# annoy-o-tron.net
KiCad netlist of a schematic drawn in EAGLE
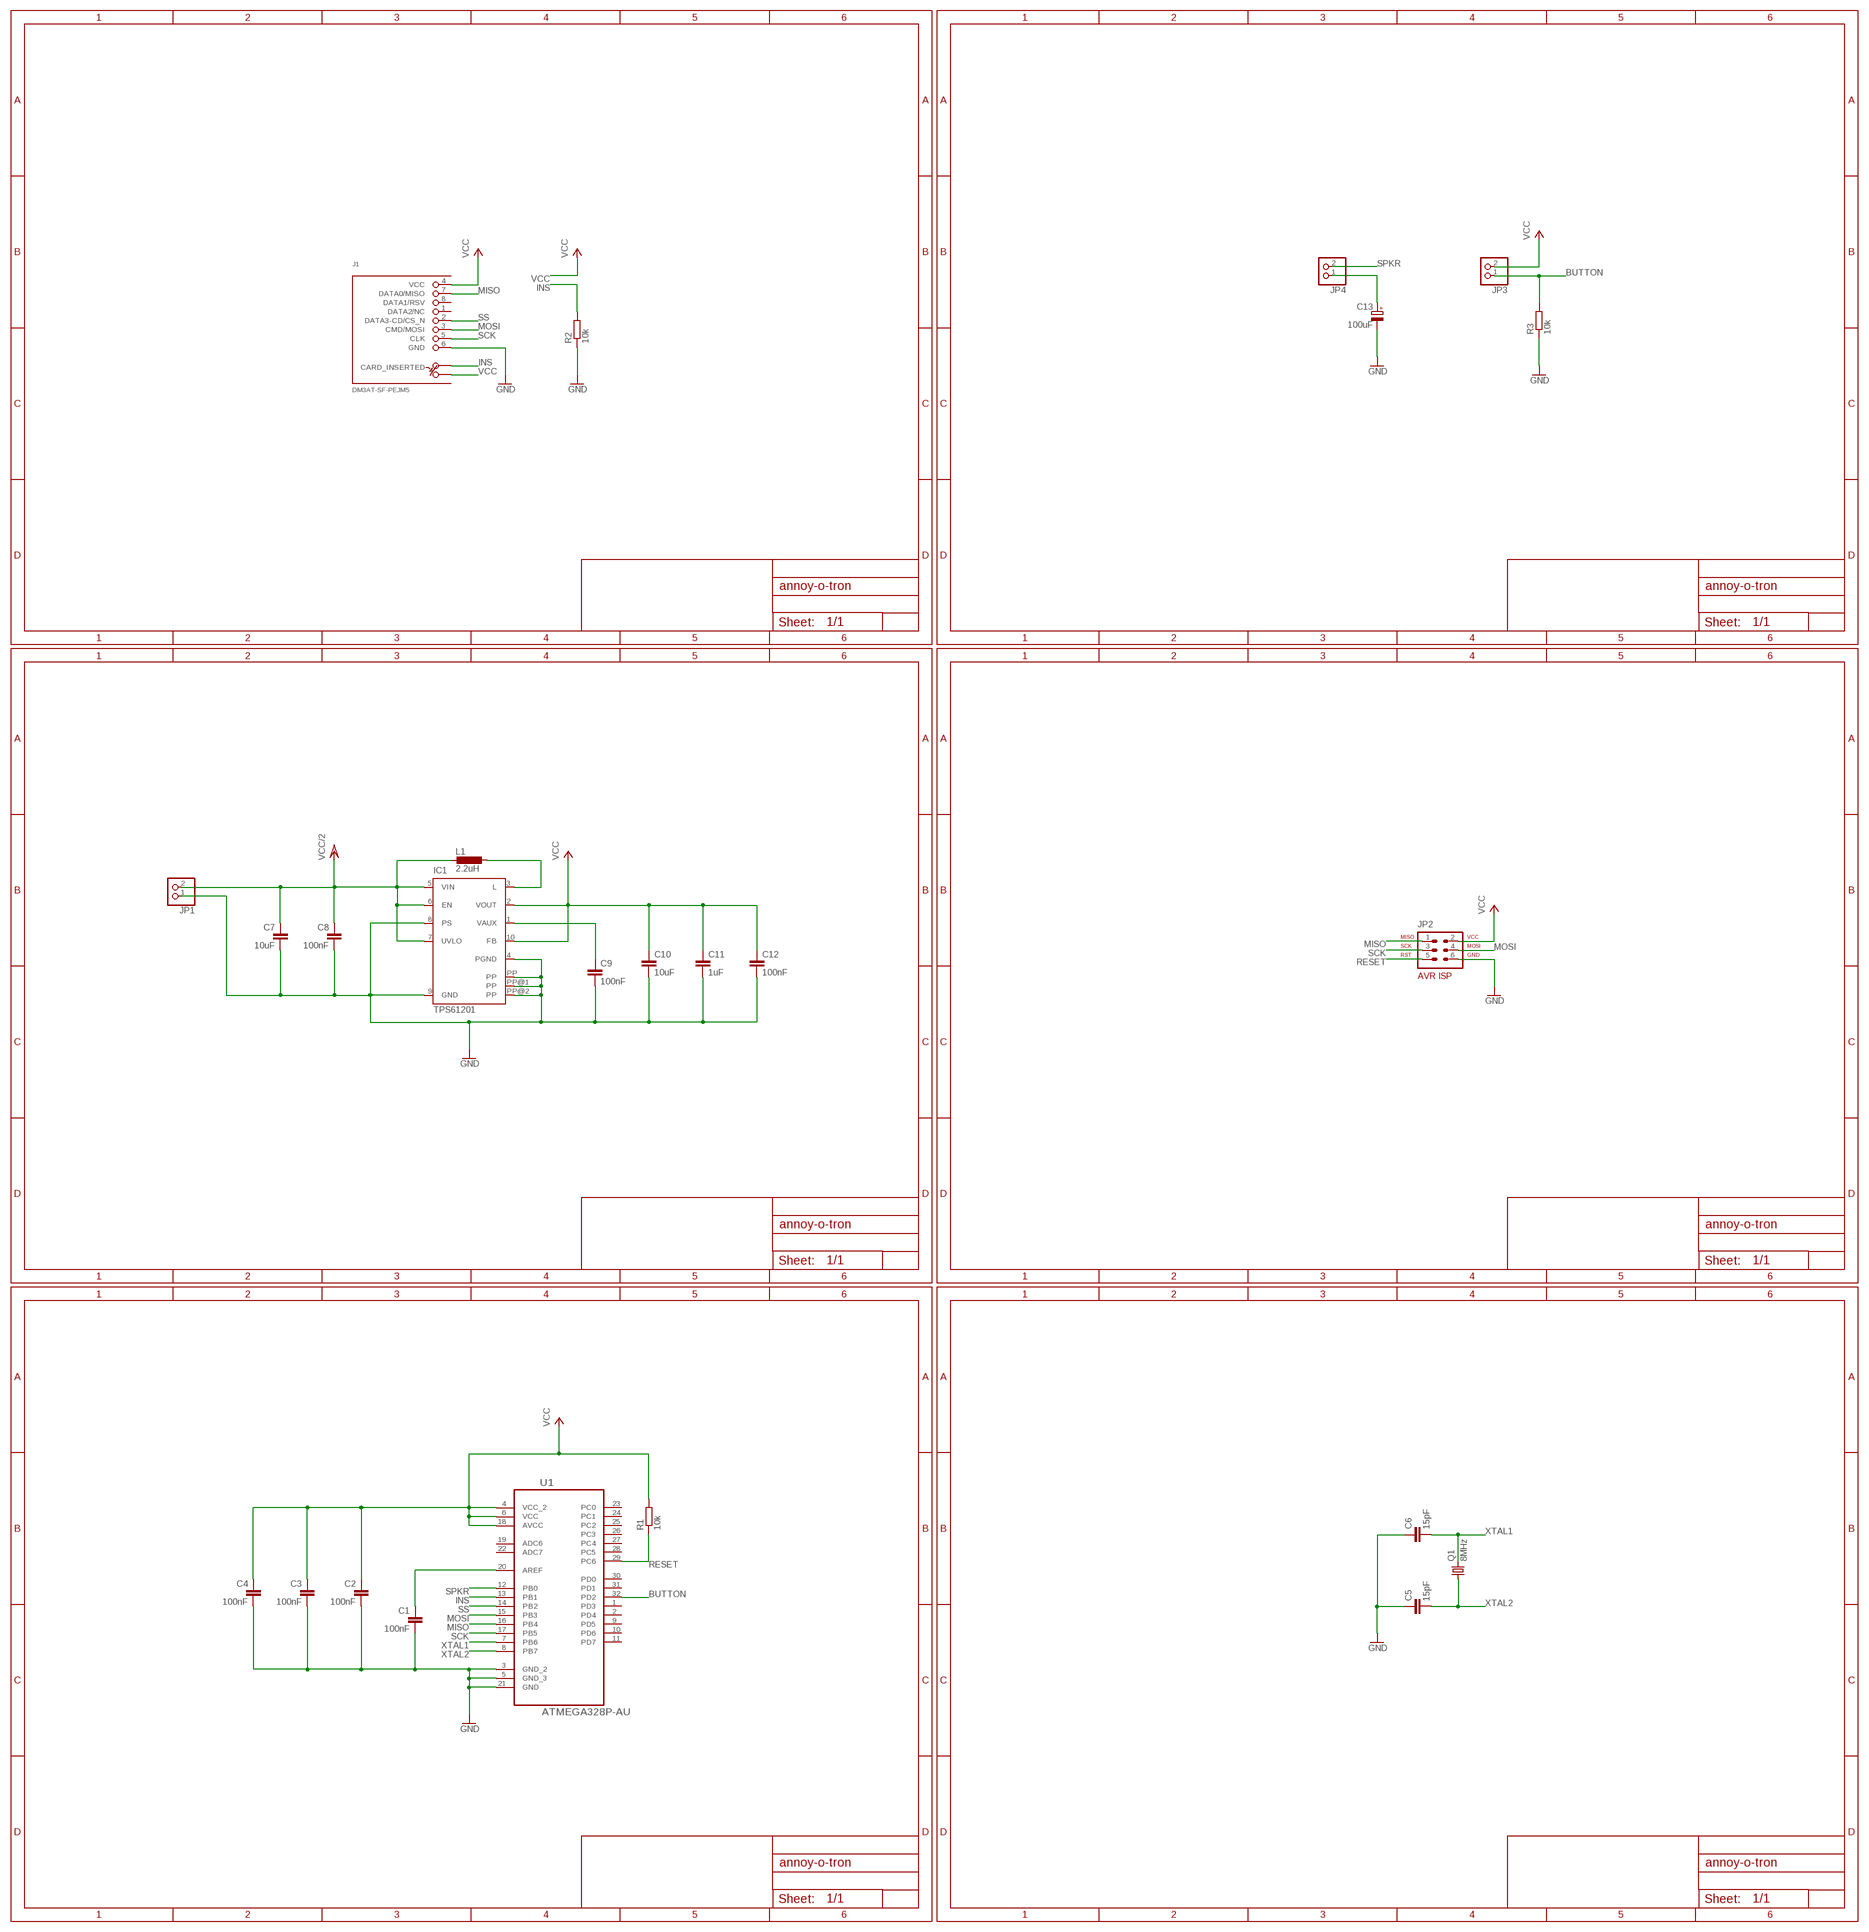
[diagram p0: schematic, sheet 1]

(export (version "E")
  (design (tool "Eeschema 10.0.6"))
  (components
    (comp (ref "C1")
      (value "100nF")
      (footprint "eagle-import:C0805K")
      (libsource (lib "eagle-import") (part "C-EUC0805K"))
    )
    (comp (ref "C2")
      (value "100nF")
      (footprint "eagle-import:C0805K")
      (libsource (lib "eagle-import") (part "C-EUC0805K"))
    )
    (comp (ref "C3")
      (value "100nF")
      (footprint "eagle-import:C0805K")
      (libsource (lib "eagle-import") (part "C-EUC0805K"))
    )
    (comp (ref "C4")
      (value "100nF")
      (footprint "eagle-import:C0805K")
      (libsource (lib "eagle-import") (part "C-EUC0805K"))
    )
    (comp (ref "C5")
      (value "15pF")
      (footprint "eagle-import:C0805K")
      (libsource (lib "eagle-import") (part "C-EUC0805K"))
    )
    (comp (ref "C6")
      (value "15pF")
      (footprint "eagle-import:C0805K")
      (libsource (lib "eagle-import") (part "C-EUC0805K"))
    )
    (comp (ref "C7")
      (value "10uF")
      (footprint "eagle-import:C0805K")
      (libsource (lib "eagle-import") (part "C-EUC0805K"))
    )
    (comp (ref "C8")
      (value "100nF")
      (footprint "eagle-import:C0805K")
      (libsource (lib "eagle-import") (part "C-EUC0805K"))
    )
    (comp (ref "C9")
      (value "100nF")
      (footprint "eagle-import:C0805K")
      (libsource (lib "eagle-import") (part "C-EUC0805K"))
    )
    (comp (ref "C10")
      (value "10uF")
      (footprint "eagle-import:C0805K")
      (libsource (lib "eagle-import") (part "C-EUC0805K"))
    )
    (comp (ref "C11")
      (value "1uF")
      (footprint "eagle-import:C0805K")
      (libsource (lib "eagle-import") (part "C-EUC0805K"))
    )
    (comp (ref "C12")
      (value "100nF")
      (footprint "eagle-import:C0805K")
      (libsource (lib "eagle-import") (part "C-EUC0805K"))
    )
    (comp (ref "C13")
      (value "100uF")
      (footprint "eagle-import:153CLV-0405")
      (libsource (lib "eagle-import") (part "CPOL-EU153CLV-0405"))
    )
    (comp (ref "IC1")
      (value "TPS61201")
      (footprint "eagle-import:S-PDSO-N10")
      (fields (field (name "MPN") "TPS61201DRCT"))
      (libsource (lib "eagle-import") (part "TPS61201"))
    )
    (comp (ref "J1")
      (value "DM3AT-SF-PEJM5")
      (footprint "eagle-import:DM3AT-SF-PEJM5")
      (libsource (lib "eagle-import") (part "DM3AT-SF-PEJM5"))
    )
    (comp (ref "JP1")
      (value "PINHD-1X2")
      (footprint "eagle-import:1X02")
      (libsource (lib "eagle-import") (part "PINHD-1X2"))
    )
    (comp (ref "JP2")
      (value "AVR-ISP-6VERT")
      (footprint "eagle-import:AVR-ISP-6")
      (libsource (lib "eagle-import") (part "AVR-ISP-6VERT"))
    )
    (comp (ref "JP3")
      (value "PINHD-1X2")
      (footprint "eagle-import:1X02")
      (libsource (lib "eagle-import") (part "PINHD-1X2"))
    )
    (comp (ref "JP4")
      (value "PINHD-1X2")
      (footprint "eagle-import:1X02")
      (libsource (lib "eagle-import") (part "PINHD-1X2"))
    )
    (comp (ref "L1")
      (value "2.2uH")
      (footprint "eagle-import:SRN3012TA")
      (libsource (lib "eagle-import") (part "SRN3012TA"))
    )
    (comp (ref "Q1")
      (value "8MHz")
      (footprint "eagle-import:HC49_S")
      (libsource (lib "eagle-import") (part "CRYSTALHC49S"))
    )
    (comp (ref "R1")
      (value "10k")
      (footprint "eagle-import:R0805")
      (libsource (lib "eagle-import") (part "R-EU_R0805"))
    )
    (comp (ref "R2")
      (value "10k")
      (footprint "eagle-import:R0805")
      (libsource (lib "eagle-import") (part "R-EU_R0805"))
    )
    (comp (ref "R3")
      (value "10k")
      (footprint "eagle-import:R0805")
      (libsource (lib "eagle-import") (part "R-EU_R0805"))
    )
    (comp (ref "U1")
      (value "ATMEGA328P-AU")
      (footprint "eagle-import:QFP80P900X900X120-32N")
      (libsource (lib "eagle-import") (part "ATMEGA328P-AU"))
    )
  )
  (nets
    (net (code "1") (name "/BUTTON") (class "Default")
      (node (ref "JP3") (pin "1") (pinfunction "1_1") (pintype "passive"))
      (node (ref "R3") (pin "2") (pinfunction "2_2") (pintype "passive"))
      (node (ref "U1") (pin "32") (pinfunction "PD2_32") (pintype "bidirectional"))
    )
    (net (code "2") (name "/INS") (class "Default")
      (node (ref "J1") (pin "A") (pinfunction "A_A") (pintype "bidirectional"))
      (node (ref "R2") (pin "2") (pinfunction "2_2") (pintype "passive"))
      (node (ref "U1") (pin "13") (pinfunction "PB1_13") (pintype "bidirectional"))
    )
    (net (code "3") (name "/MISO") (class "Default")
      (node (ref "J1") (pin "7") (pinfunction "DATA0/MISO_7") (pintype "bidirectional"))
      (node (ref "JP2") (pin "1") (pinfunction "1_1") (pintype "passive"))
      (node (ref "U1") (pin "16") (pinfunction "PB4_16") (pintype "bidirectional"))
    )
    (net (code "4") (name "/MOSI") (class "Default")
      (node (ref "J1") (pin "3") (pinfunction "CMD/MOSI_3") (pintype "bidirectional"))
      (node (ref "JP2") (pin "4") (pinfunction "4_4") (pintype "passive"))
      (node (ref "U1") (pin "15") (pinfunction "PB3_15") (pintype "bidirectional"))
    )
    (net (code "5") (name "/RESET") (class "Default")
      (node (ref "JP2") (pin "5") (pinfunction "5_5") (pintype "passive"))
      (node (ref "R1") (pin "1") (pinfunction "1_1") (pintype "passive"))
      (node (ref "U1") (pin "29") (pinfunction "PC6_29") (pintype "bidirectional"))
    )
    (net (code "6") (name "/SCK") (class "Default")
      (node (ref "J1") (pin "5") (pinfunction "CLK_5") (pintype "bidirectional"))
      (node (ref "JP2") (pin "3") (pinfunction "3_3") (pintype "passive"))
      (node (ref "U1") (pin "17") (pinfunction "PB5_17") (pintype "bidirectional"))
    )
    (net (code "7") (name "/SPKR") (class "Default")
      (node (ref "JP4") (pin "2") (pinfunction "2_2") (pintype "passive"))
      (node (ref "U1") (pin "12") (pinfunction "PB0_12") (pintype "bidirectional"))
    )
    (net (code "8") (name "/SS") (class "Default")
      (node (ref "J1") (pin "2") (pinfunction "DATA3-CD/CS_N_2") (pintype "bidirectional"))
      (node (ref "U1") (pin "14") (pinfunction "PB2_14") (pintype "bidirectional"))
    )
    (net (code "9") (name "/XTAL1") (class "Default")
      (node (ref "C6") (pin "2") (pinfunction "2_2") (pintype "passive"))
      (node (ref "Q1") (pin "2") (pinfunction "2_2") (pintype "passive"))
      (node (ref "U1") (pin "7") (pinfunction "PB6_7") (pintype "bidirectional"))
    )
    (net (code "10") (name "/XTAL2") (class "Default")
      (node (ref "C5") (pin "2") (pinfunction "2_2") (pintype "passive"))
      (node (ref "Q1") (pin "1") (pinfunction "1_1") (pintype "passive"))
      (node (ref "U1") (pin "8") (pinfunction "PB7_8") (pintype "bidirectional"))
    )
    (net (code "11") (name "GND") (class "Default")
      (node (ref "C1") (pin "2") (pinfunction "2_2") (pintype "passive"))
      (node (ref "C10") (pin "2") (pinfunction "2_2") (pintype "passive"))
      (node (ref "C11") (pin "2") (pinfunction "2_2") (pintype "passive"))
      (node (ref "C12") (pin "2") (pinfunction "2_2") (pintype "passive"))
      (node (ref "C13") (pin "-") (pinfunction "-_-") (pintype "passive"))
      (node (ref "C2") (pin "2") (pinfunction "2_2") (pintype "passive"))
      (node (ref "C3") (pin "2") (pinfunction "2_2") (pintype "passive"))
      (node (ref "C4") (pin "2") (pinfunction "2_2") (pintype "passive"))
      (node (ref "C5") (pin "1") (pinfunction "1_1") (pintype "passive"))
      (node (ref "C6") (pin "1") (pinfunction "1_1") (pintype "passive"))
      (node (ref "C7") (pin "2") (pinfunction "2_2") (pintype "passive"))
      (node (ref "C8") (pin "2") (pinfunction "2_2") (pintype "passive"))
      (node (ref "C9") (pin "2") (pinfunction "2_2") (pintype "passive"))
      (node (ref "IC1") (pin "4") (pinfunction "PGND_4") (pintype "power_in"))
      (node (ref "IC1") (pin "8") (pinfunction "PS_8") (pintype "input"))
      (node (ref "IC1") (pin "9") (pinfunction "GND_9") (pintype "power_in"))
      (node (ref "IC1") (pin "PP") (pinfunction "PP_PP") (pintype "power_in"))
      (node (ref "IC1") (pin "PP@1") (pinfunction "PP_PP@1") (pintype "power_in"))
      (node (ref "IC1") (pin "PP@2") (pinfunction "PP_PP@2") (pintype "power_in"))
      (node (ref "J1") (pin "6") (pinfunction "GND_6") (pintype "bidirectional"))
      (node (ref "JP1") (pin "1") (pinfunction "1_1") (pintype "passive"))
      (node (ref "JP2") (pin "6") (pinfunction "6_6") (pintype "passive"))
      (node (ref "R2") (pin "1") (pinfunction "1_1") (pintype "passive"))
      (node (ref "R3") (pin "1") (pinfunction "1_1") (pintype "passive"))
      (node (ref "U1") (pin "21") (pinfunction "GND_21") (pintype "passive"))
      (node (ref "U1") (pin "3") (pinfunction "GND_2_3") (pintype "passive"))
      (node (ref "U1") (pin "5") (pinfunction "GND_3_5") (pintype "passive"))
    )
    (net (code "12") (name "Net-(C13-Pad+)") (class "Default")
      (node (ref "C13") (pin "+") (pinfunction "+_+") (pintype "passive"))
      (node (ref "JP4") (pin "1") (pinfunction "1_1") (pintype "passive"))
    )
    (net (code "13") (name "Net-(IC1-L)") (class "Default")
      (node (ref "IC1") (pin "3") (pinfunction "L_3") (pintype "input"))
      (node (ref "L1") (pin "P$1") (pinfunction "1_P$1") (pintype "passive"))
    )
    (net (code "14") (name "Net-(IC1-VAUX)") (class "Default")
      (node (ref "C9") (pin "1") (pinfunction "1_1") (pintype "passive"))
      (node (ref "IC1") (pin "1") (pinfunction "VAUX_1") (pintype "bidirectional"))
    )
    (net (code "15") (name "Net-(U1-AREF)") (class "Default")
      (node (ref "C1") (pin "1") (pinfunction "1_1") (pintype "passive"))
      (node (ref "U1") (pin "20") (pinfunction "AREF_20") (pintype "input"))
    )
    (net (code "16") (name "VCC") (class "Default")
      (node (ref "C10") (pin "1") (pinfunction "1_1") (pintype "passive"))
      (node (ref "C11") (pin "1") (pinfunction "1_1") (pintype "passive"))
      (node (ref "C12") (pin "1") (pinfunction "1_1") (pintype "passive"))
      (node (ref "C2") (pin "1") (pinfunction "1_1") (pintype "passive"))
      (node (ref "C3") (pin "1") (pinfunction "1_1") (pintype "passive"))
      (node (ref "C4") (pin "1") (pinfunction "1_1") (pintype "passive"))
      (node (ref "IC1") (pin "10") (pinfunction "FB_10") (pintype "input"))
      (node (ref "IC1") (pin "2") (pinfunction "VOUT_2") (pintype "passive"))
      (node (ref "J1") (pin "4") (pinfunction "VCC_4") (pintype "bidirectional"))
      (node (ref "J1") (pin "B") (pinfunction "B_B") (pintype "bidirectional"))
      (node (ref "JP2") (pin "2") (pinfunction "2_2") (pintype "passive"))
      (node (ref "JP3") (pin "2") (pinfunction "2_2") (pintype "passive"))
      (node (ref "R1") (pin "2") (pinfunction "2_2") (pintype "passive"))
      (node (ref "U1") (pin "18") (pinfunction "AVCC_18") (pintype "power_in"))
      (node (ref "U1") (pin "4") (pinfunction "VCC_2_4") (pintype "power_in"))
      (node (ref "U1") (pin "6") (pinfunction "VCC_6") (pintype "power_in"))
    )
    (net (code "17") (name "VCC{slash}2") (class "Default")
      (node (ref "C7") (pin "1") (pinfunction "1_1") (pintype "passive"))
      (node (ref "C8") (pin "1") (pinfunction "1_1") (pintype "passive"))
      (node (ref "IC1") (pin "5") (pinfunction "VIN_5") (pintype "input"))
      (node (ref "IC1") (pin "6") (pinfunction "EN_6") (pintype "input"))
      (node (ref "IC1") (pin "7") (pinfunction "UVLO_7") (pintype "input"))
      (node (ref "JP1") (pin "2") (pinfunction "2_2") (pintype "passive"))
      (node (ref "L1") (pin "P$2") (pinfunction "2_P$2") (pintype "passive"))
    )
    (net (code "18") (name "unconnected-(J1-DATA1{slash}RSV-Pad8)") (class "Default")
      (node (ref "J1") (pin "8") (pinfunction "DATA1/RSV_8") (pintype "bidirectional"))
    )
    (net (code "19") (name "unconnected-(J1-DATA2{slash}NC-Pad1)") (class "Default")
      (node (ref "J1") (pin "1") (pinfunction "DATA2/NC_1") (pintype "bidirectional"))
    )
    (net (code "20") (name "unconnected-(U1-ADC6-Pad19)") (class "Default")
      (node (ref "U1") (pin "19") (pinfunction "ADC6_19") (pintype "input"))
    )
    (net (code "21") (name "unconnected-(U1-ADC7-Pad22)") (class "Default")
      (node (ref "U1") (pin "22") (pinfunction "ADC7_22") (pintype "input"))
    )
    (net (code "22") (name "unconnected-(U1-PC0-Pad23)") (class "Default")
      (node (ref "U1") (pin "23") (pinfunction "PC0_23") (pintype "bidirectional"))
    )
    (net (code "23") (name "unconnected-(U1-PC1-Pad24)") (class "Default")
      (node (ref "U1") (pin "24") (pinfunction "PC1_24") (pintype "bidirectional"))
    )
    (net (code "24") (name "unconnected-(U1-PC2-Pad25)") (class "Default")
      (node (ref "U1") (pin "25") (pinfunction "PC2_25") (pintype "bidirectional"))
    )
    (net (code "25") (name "unconnected-(U1-PC3-Pad26)") (class "Default")
      (node (ref "U1") (pin "26") (pinfunction "PC3_26") (pintype "bidirectional"))
    )
    (net (code "26") (name "unconnected-(U1-PC4-Pad27)") (class "Default")
      (node (ref "U1") (pin "27") (pinfunction "PC4_27") (pintype "bidirectional"))
    )
    (net (code "27") (name "unconnected-(U1-PC5-Pad28)") (class "Default")
      (node (ref "U1") (pin "28") (pinfunction "PC5_28") (pintype "bidirectional"))
    )
    (net (code "28") (name "unconnected-(U1-PD0-Pad30)") (class "Default")
      (node (ref "U1") (pin "30") (pinfunction "PD0_30") (pintype "bidirectional"))
    )
    (net (code "29") (name "unconnected-(U1-PD1-Pad31)") (class "Default")
      (node (ref "U1") (pin "31") (pinfunction "PD1_31") (pintype "bidirectional"))
    )
    (net (code "30") (name "unconnected-(U1-PD3-Pad1)") (class "Default")
      (node (ref "U1") (pin "1") (pinfunction "PD3_1") (pintype "bidirectional"))
    )
    (net (code "31") (name "unconnected-(U1-PD4-Pad2)") (class "Default")
      (node (ref "U1") (pin "2") (pinfunction "PD4_2") (pintype "bidirectional"))
    )
    (net (code "32") (name "unconnected-(U1-PD5-Pad9)") (class "Default")
      (node (ref "U1") (pin "9") (pinfunction "PD5_9") (pintype "bidirectional"))
    )
    (net (code "33") (name "unconnected-(U1-PD6-Pad10)") (class "Default")
      (node (ref "U1") (pin "10") (pinfunction "PD6_10") (pintype "bidirectional"))
    )
    (net (code "34") (name "unconnected-(U1-PD7-Pad11)") (class "Default")
      (node (ref "U1") (pin "11") (pinfunction "PD7_11") (pintype "bidirectional"))
    )
  )
)
